# Reflow_Control_Board.net
KiCad netlist of a schematic drawn in EAGLE
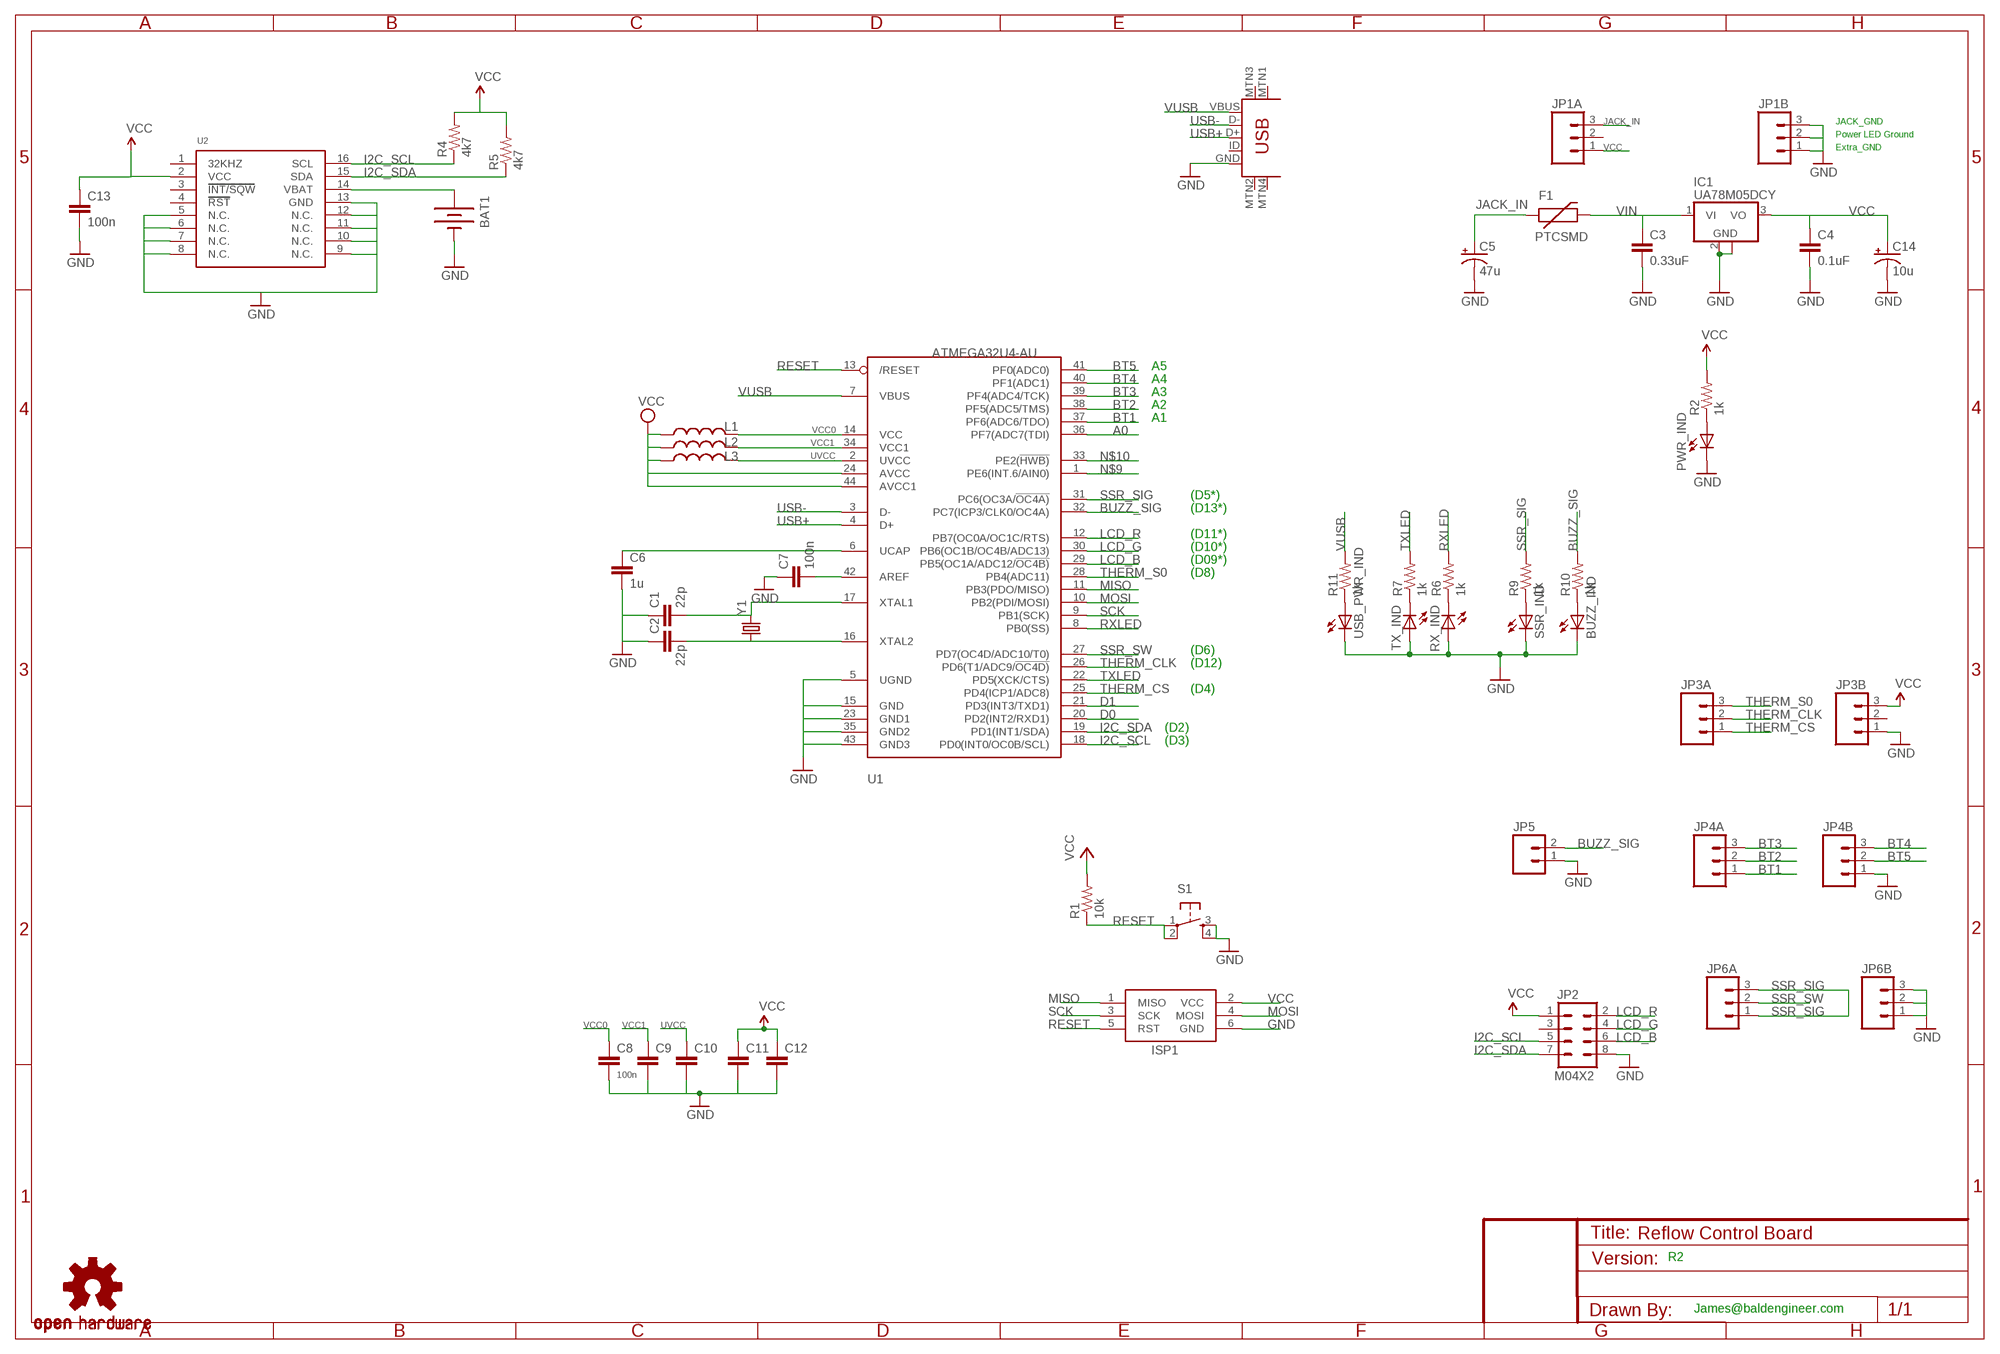
[diagram p0: schematic, sheet 1]

(export (version "E")
  (design (tool "Eeschema 10.0.6"))
  (components
    (comp (ref "BAT1")
      (value "BATTERY12MM")
      (footprint "eagle-import:BATTCON_12MM")
      (libsource (lib "eagle-import") (part "BATTERY12MM"))
    )
    (comp (ref "BUZZ_IND")
      (value "LED1206")
      (footprint "eagle-import:LED-1206")
      (libsource (lib "eagle-import") (part "LED1206"))
    )
    (comp (ref "C1")
      (value "22p")
      (footprint "eagle-import:1206")
      (libsource (lib "eagle-import") (part "CAP1206"))
    )
    (comp (ref "C2")
      (value "22p")
      (footprint "eagle-import:1206")
      (libsource (lib "eagle-import") (part "CAP1206"))
    )
    (comp (ref "C3")
      (value "0.33uF")
      (footprint "eagle-import:1206")
      (libsource (lib "eagle-import") (part "CAP1206"))
    )
    (comp (ref "C4")
      (value "0.1uF")
      (footprint "eagle-import:1206")
      (libsource (lib "eagle-import") (part "CAP1206"))
    )
    (comp (ref "C5")
      (value "47u")
      (footprint "eagle-import:D_7343-31R")
      (libsource (lib "eagle-import") (part "CPOL-USD/7343-31R"))
    )
    (comp (ref "C6")
      (value "1u")
      (footprint "eagle-import:1206")
      (libsource (lib "eagle-import") (part "CAP1206"))
    )
    (comp (ref "C7")
      (value "100n")
      (footprint "eagle-import:1206")
      (libsource (lib "eagle-import") (part "CAP1206"))
    )
    (comp (ref "C8")
      (value "100n")
      (footprint "eagle-import:1206")
      (libsource (lib "eagle-import") (part "CAP1206"))
    )
    (comp (ref "C9")
      (value "100n")
      (footprint "eagle-import:1206")
      (libsource (lib "eagle-import") (part "CAP1206"))
    )
    (comp (ref "C10")
      (value "100n")
      (footprint "eagle-import:1206")
      (libsource (lib "eagle-import") (part "CAP1206"))
    )
    (comp (ref "C11")
      (value "100n")
      (footprint "eagle-import:1206")
      (libsource (lib "eagle-import") (part "CAP1206"))
    )
    (comp (ref "C12")
      (value "100n")
      (footprint "eagle-import:1206")
      (libsource (lib "eagle-import") (part "CAP1206"))
    )
    (comp (ref "C13")
      (value "100n")
      (footprint "eagle-import:1206")
      (libsource (lib "eagle-import") (part "CAP1206"))
    )
    (comp (ref "C14")
      (value "10u")
      (footprint "eagle-import:D_7343-31R")
      (libsource (lib "eagle-import") (part "CPOL-USD/7343-31R"))
    )
    (comp (ref "F1")
      (value "PTCSMD")
      (footprint "eagle-import:PTC-1206")
      (libsource (lib "eagle-import") (part "PTCSMD"))
    )
    (comp (ref "IC1")
      (value "UA78M05DCY")
      (footprint "eagle-import:SOT223")
      (libsource (lib "eagle-import") (part "UA78MDCY05"))
    )
    (comp (ref "ISP1")
      (value "AVRISP-6")
      (footprint "eagle-import:AVRISP")
      (libsource (lib "eagle-import") (part "AVRISP-6"))
    )
    (comp (ref "JP1A")
      (value "M03LOCK")
      (footprint "eagle-import:1X03_LOCK")
      (libsource (lib "eagle-import") (part "M03LOCK"))
    )
    (comp (ref "JP1B")
      (value "M03LOCK")
      (footprint "eagle-import:1X03_LOCK")
      (libsource (lib "eagle-import") (part "M03LOCK"))
    )
    (comp (ref "JP2")
      (value "M04X2")
      (footprint "eagle-import:2X4")
      (libsource (lib "eagle-import") (part "M04X2"))
    )
    (comp (ref "JP3A")
      (value "M03LOCK")
      (footprint "eagle-import:1X03_LOCK")
      (libsource (lib "eagle-import") (part "M03LOCK"))
    )
    (comp (ref "JP3B")
      (value "M03LOCK")
      (footprint "eagle-import:1X03_LOCK")
      (libsource (lib "eagle-import") (part "M03LOCK"))
    )
    (comp (ref "JP4A")
      (value "M03LOCK")
      (footprint "eagle-import:1X03_LOCK")
      (libsource (lib "eagle-import") (part "M03LOCK"))
    )
    (comp (ref "JP4B")
      (value "M03LOCK")
      (footprint "eagle-import:1X03_LOCK")
      (libsource (lib "eagle-import") (part "M03LOCK"))
    )
    (comp (ref "JP5")
      (value "M02LOCK")
      (footprint "eagle-import:1X02_LOCK")
      (libsource (lib "eagle-import") (part "M02LOCK"))
    )
    (comp (ref "JP6A")
      (value "M03LOCK")
      (footprint "eagle-import:1X03_LOCK")
      (libsource (lib "eagle-import") (part "M03LOCK"))
    )
    (comp (ref "JP6B")
      (value "M03LOCK")
      (footprint "eagle-import:1X03_LOCK")
      (libsource (lib "eagle-import") (part "M03LOCK"))
    )
    (comp (ref "L1")
      (value "INDUCTOR0805")
      (footprint "eagle-import:0805")
      (libsource (lib "eagle-import") (part "INDUCTOR0805"))
    )
    (comp (ref "L2")
      (value "INDUCTOR0805")
      (footprint "eagle-import:0805")
      (libsource (lib "eagle-import") (part "INDUCTOR0805"))
    )
    (comp (ref "L3")
      (value "INDUCTOR0805")
      (footprint "eagle-import:0805")
      (libsource (lib "eagle-import") (part "INDUCTOR0805"))
    )
    (comp (ref "PWR_IND")
      (value "LED1206")
      (footprint "eagle-import:LED-1206")
      (libsource (lib "eagle-import") (part "LED1206"))
    )
    (comp (ref "R1")
      (value "10k")
      (footprint "eagle-import:1206")
      (libsource (lib "eagle-import") (part "RESISTOR1206"))
    )
    (comp (ref "R2")
      (value "1k")
      (footprint "eagle-import:1206")
      (libsource (lib "eagle-import") (part "RESISTOR1206"))
    )
    (comp (ref "R4")
      (value "4k7")
      (footprint "eagle-import:1206")
      (libsource (lib "eagle-import") (part "RESISTOR1206"))
    )
    (comp (ref "R5")
      (value "4k7")
      (footprint "eagle-import:1206")
      (libsource (lib "eagle-import") (part "RESISTOR1206"))
    )
    (comp (ref "R6")
      (value "1k")
      (footprint "eagle-import:1206")
      (libsource (lib "eagle-import") (part "RESISTOR1206"))
    )
    (comp (ref "R7")
      (value "1k")
      (footprint "eagle-import:1206")
      (libsource (lib "eagle-import") (part "RESISTOR1206"))
    )
    (comp (ref "R9")
      (value "1k")
      (footprint "eagle-import:1206")
      (libsource (lib "eagle-import") (part "RESISTOR1206"))
    )
    (comp (ref "R10")
      (value "1k")
      (footprint "eagle-import:1206")
      (libsource (lib "eagle-import") (part "RESISTOR1206"))
    )
    (comp (ref "R11")
      (value "1k")
      (footprint "eagle-import:1206")
      (libsource (lib "eagle-import") (part "RESISTOR1206"))
    )
    (comp (ref "RX_IND")
      (value "LED1206")
      (footprint "eagle-import:LED-1206")
      (libsource (lib "eagle-import") (part "LED1206"))
    )
    (comp (ref "S1")
      (value "TAC_SWITCHSMD")
      (footprint "eagle-import:TACTILE_SWITCH_SMD")
      (libsource (lib "eagle-import") (part "TAC_SWITCHSMD"))
    )
    (comp (ref "SSR_IND")
      (value "LED1206")
      (footprint "eagle-import:LED-1206")
      (libsource (lib "eagle-import") (part "LED1206"))
    )
    (comp (ref "TX_IND")
      (value "LED1206")
      (footprint "eagle-import:LED-1206")
      (libsource (lib "eagle-import") (part "LED1206"))
    )
    (comp (ref "U$3")
      (value "USB-MINIB-5PIN")
      (footprint "eagle-import:USB-MINIB")
      (libsource (lib "eagle-import") (part "USB-MINIB-5PIN"))
    )
    (comp (ref "U$4")
      (value "OSHW-LOGOS")
      (footprint "eagle-import:OSHW-LOGO-S")
      (libsource (lib "eagle-import") (part "OSHW-LOGOS"))
    )
    (comp (ref "U1")
      (value "ATMEGA32U4-AU")
      (footprint "eagle-import:TQFP44")
      (libsource (lib "eagle-import") (part "ATMEGA32U4-AU"))
    )
    (comp (ref "U2")
      (value "DS3231")
      (footprint "eagle-import:SO16L")
      (libsource (lib "eagle-import") (part "DS3231"))
    )
    (comp (ref "USB_PWR_IND")
      (value "LED1206")
      (footprint "eagle-import:LED-1206")
      (libsource (lib "eagle-import") (part "LED1206"))
    )
    (comp (ref "Y1")
      (value "CRYSTALHC49US")
      (footprint "eagle-import:HC49US")
      (libsource (lib "eagle-import") (part "CRYSTALHC49US"))
    )
  )
  (nets
    (net (code "1") (name "/A0") (class "Default")
      (node (ref "U1") (pin "36") (pinfunction "PF7(ADC7(TDI)_36") (pintype "bidirectional"))
    )
    (net (code "2") (name "/BT1") (class "Default")
      (node (ref "JP4A") (pin "1") (pinfunction "1_1") (pintype "passive"))
      (node (ref "U1") (pin "37") (pinfunction "PF6(ADC6/TDO)_37") (pintype "bidirectional"))
    )
    (net (code "3") (name "/BT2") (class "Default")
      (node (ref "JP4A") (pin "2") (pinfunction "2_2") (pintype "passive"))
      (node (ref "U1") (pin "38") (pinfunction "PF5(ADC5/TMS)_38") (pintype "bidirectional"))
    )
    (net (code "4") (name "/BT3") (class "Default")
      (node (ref "JP4A") (pin "3") (pinfunction "3_3") (pintype "passive"))
      (node (ref "U1") (pin "39") (pinfunction "PF4(ADC4/TCK)_39") (pintype "bidirectional"))
    )
    (net (code "5") (name "/BT4") (class "Default")
      (node (ref "JP4B") (pin "3") (pinfunction "3_3") (pintype "passive"))
      (node (ref "U1") (pin "40") (pinfunction "PF1(ADC1)_40") (pintype "bidirectional"))
    )
    (net (code "6") (name "/BT5") (class "Default")
      (node (ref "JP4B") (pin "2") (pinfunction "2_2") (pintype "passive"))
      (node (ref "U1") (pin "41") (pinfunction "PF0(ADC0)_41") (pintype "bidirectional"))
    )
    (net (code "7") (name "/BUZZ_SIG") (class "Default")
      (node (ref "JP5") (pin "2") (pinfunction "2_2") (pintype "passive"))
      (node (ref "R10") (pin "2") (pinfunction "2_2") (pintype "passive"))
      (node (ref "U1") (pin "32") (pinfunction "PC7(ICP3/CLK0/OC4A)_32") (pintype "bidirectional"))
    )
    (net (code "8") (name "/D0") (class "Default")
      (node (ref "U1") (pin "20") (pinfunction "PD2(INT2/RXD1)_20") (pintype "bidirectional"))
    )
    (net (code "9") (name "/D1") (class "Default")
      (node (ref "U1") (pin "21") (pinfunction "PD3(INT3/TXD1)_21") (pintype "bidirectional"))
    )
    (net (code "10") (name "/I2C_SCL") (class "Default")
      (node (ref "JP2") (pin "5") (pinfunction "5_5") (pintype "passive"))
      (node (ref "R4") (pin "1") (pinfunction "1_1") (pintype "passive"))
      (node (ref "U1") (pin "18") (pinfunction "PD0(INT0/OC0B/SCL)_18") (pintype "bidirectional"))
      (node (ref "U2") (pin "16") (pinfunction "SCL_16") (pintype "bidirectional"))
    )
    (net (code "11") (name "/I2C_SDA") (class "Default")
      (node (ref "JP2") (pin "7") (pinfunction "7_7") (pintype "passive"))
      (node (ref "R5") (pin "1") (pinfunction "1_1") (pintype "passive"))
      (node (ref "U1") (pin "19") (pinfunction "PD1(INT1/SDA)_19") (pintype "bidirectional"))
      (node (ref "U2") (pin "15") (pinfunction "SDA_15") (pintype "bidirectional"))
    )
    (net (code "12") (name "/JACK_IN") (class "Default")
      (node (ref "C5") (pin "+") (pinfunction "+_+") (pintype "passive"))
      (node (ref "F1") (pin "1") (pinfunction "1_1") (pintype "bidirectional"))
      (node (ref "JP1A") (pin "3") (pinfunction "3_3") (pintype "passive"))
    )
    (net (code "13") (name "/LCD_B") (class "Default")
      (node (ref "JP2") (pin "6") (pinfunction "6_6") (pintype "passive"))
      (node (ref "U1") (pin "29") (pinfunction "PB5(OC1A/ADC12/~{OC4B})_29") (pintype "bidirectional"))
    )
    (net (code "14") (name "/LCD_G") (class "Default")
      (node (ref "JP2") (pin "4") (pinfunction "4_4") (pintype "passive"))
      (node (ref "U1") (pin "30") (pinfunction "PB6(OC1B/OC4B/ADC13)_30") (pintype "bidirectional"))
    )
    (net (code "15") (name "/LCD_R") (class "Default")
      (node (ref "JP2") (pin "2") (pinfunction "2_2") (pintype "passive"))
      (node (ref "U1") (pin "12") (pinfunction "PB7(OC0A/OC1C/RTS)_12") (pintype "bidirectional"))
    )
    (net (code "16") (name "/MISO") (class "Default")
      (node (ref "ISP1") (pin "1") (pinfunction "MISO_1") (pintype "input"))
      (node (ref "U1") (pin "11") (pinfunction "PB3(PDO/MISO)_11") (pintype "bidirectional"))
    )
    (net (code "17") (name "/MOSI") (class "Default")
      (node (ref "ISP1") (pin "4") (pinfunction "MOSI_4") (pintype "output"))
      (node (ref "U1") (pin "10") (pinfunction "PB2(PDI/MOSI)_10") (pintype "bidirectional"))
    )
    (net (code "18") (name "/N$9") (class "Default")
      (node (ref "U1") (pin "1") (pinfunction "PE6(INT.6/AIN0)_1") (pintype "bidirectional"))
    )
    (net (code "19") (name "/N$10") (class "Default")
      (node (ref "U1") (pin "33") (pinfunction "PE2(~{HWB})_33") (pintype "bidirectional"))
    )
    (net (code "20") (name "/RESET") (class "Default")
      (node (ref "ISP1") (pin "5") (pinfunction "RST_5") (pintype "output"))
      (node (ref "R1") (pin "1") (pinfunction "1_1") (pintype "passive"))
      (node (ref "S1") (pin "1") (pinfunction "1_1") (pintype "passive"))
      (node (ref "S1") (pin "2") (pinfunction "2_2") (pintype "passive"))
      (node (ref "U1") (pin "13") (pinfunction "/RESET_13") (pintype "bidirectional"))
    )
    (net (code "21") (name "/RXLED") (class "Default")
      (node (ref "R6") (pin "2") (pinfunction "2_2") (pintype "passive"))
      (node (ref "U1") (pin "8") (pinfunction "PB0(SS)_8") (pintype "bidirectional"))
    )
    (net (code "22") (name "/SCK") (class "Default")
      (node (ref "ISP1") (pin "3") (pinfunction "SCK_3") (pintype "output"))
      (node (ref "U1") (pin "9") (pinfunction "PB1(SCK)_9") (pintype "bidirectional"))
    )
    (net (code "23") (name "/SSR_SIG") (class "Default")
      (node (ref "JP6A") (pin "1") (pinfunction "1_1") (pintype "passive"))
      (node (ref "JP6A") (pin "3") (pinfunction "3_3") (pintype "passive"))
      (node (ref "R9") (pin "2") (pinfunction "2_2") (pintype "passive"))
      (node (ref "U1") (pin "31") (pinfunction "PC6(OC3A/~{OC4A})_31") (pintype "bidirectional"))
    )
    (net (code "24") (name "/SSR_SW") (class "Default")
      (node (ref "JP6A") (pin "2") (pinfunction "2_2") (pintype "passive"))
      (node (ref "U1") (pin "27") (pinfunction "PD7(OC4D/ADC10/T0)_27") (pintype "bidirectional"))
    )
    (net (code "25") (name "/THERM_CLK") (class "Default")
      (node (ref "JP3A") (pin "2") (pinfunction "2_2") (pintype "passive"))
      (node (ref "U1") (pin "26") (pinfunction "PD6(T1/ADC9/~{OC4D})_26") (pintype "bidirectional"))
    )
    (net (code "26") (name "/THERM_CS") (class "Default")
      (node (ref "JP3A") (pin "1") (pinfunction "1_1") (pintype "passive"))
      (node (ref "U1") (pin "25") (pinfunction "PD4(ICP1/ADC8)_25") (pintype "bidirectional"))
    )
    (net (code "27") (name "/THERM_S0") (class "Default")
      (node (ref "JP3A") (pin "3") (pinfunction "3_3") (pintype "passive"))
      (node (ref "U1") (pin "28") (pinfunction "PB4(ADC11)_28") (pintype "bidirectional"))
    )
    (net (code "28") (name "/TXLED") (class "Default")
      (node (ref "R7") (pin "2") (pinfunction "2_2") (pintype "passive"))
      (node (ref "U1") (pin "22") (pinfunction "PD5(XCK/CTS)_22") (pintype "bidirectional"))
    )
    (net (code "29") (name "/USB+") (class "Default")
      (node (ref "U$3") (pin "D+") (pinfunction "D+_D+") (pintype "bidirectional"))
      (node (ref "U1") (pin "4") (pinfunction "D+_4") (pintype "bidirectional"))
    )
    (net (code "30") (name "/USB-") (class "Default")
      (node (ref "U$3") (pin "D-") (pinfunction "D-_D-") (pintype "bidirectional"))
      (node (ref "U1") (pin "3") (pinfunction "D-_3") (pintype "bidirectional"))
    )
    (net (code "31") (name "/UVCC") (class "Default")
      (node (ref "C10") (pin "1") (pinfunction "1_1") (pintype "passive"))
      (node (ref "L3") (pin "2") (pinfunction "2_2") (pintype "passive"))
      (node (ref "U1") (pin "2") (pinfunction "UVCC_2") (pintype "bidirectional"))
    )
    (net (code "32") (name "/VCC0") (class "Default")
      (node (ref "C8") (pin "1") (pinfunction "1_1") (pintype "passive"))
      (node (ref "L1") (pin "2") (pinfunction "2_2") (pintype "passive"))
      (node (ref "U1") (pin "14") (pinfunction "VCC_14") (pintype "bidirectional"))
    )
    (net (code "33") (name "/VCC1") (class "Default")
      (node (ref "C9") (pin "1") (pinfunction "1_1") (pintype "passive"))
      (node (ref "L2") (pin "2") (pinfunction "2_2") (pintype "passive"))
      (node (ref "U1") (pin "34") (pinfunction "VCC1_34") (pintype "bidirectional"))
    )
    (net (code "34") (name "/VIN") (class "Default")
      (node (ref "C3") (pin "1") (pinfunction "1_1") (pintype "passive"))
      (node (ref "F1") (pin "2") (pinfunction "2_2") (pintype "bidirectional"))
      (node (ref "IC1") (pin "1") (pinfunction "VI_1") (pintype "input"))
    )
    (net (code "35") (name "/VUSB") (class "Default")
      (node (ref "R11") (pin "2") (pinfunction "2_2") (pintype "passive"))
      (node (ref "U$3") (pin "VBUS") (pinfunction "VBUS_VBUS") (pintype "bidirectional"))
      (node (ref "U1") (pin "7") (pinfunction "VBUS_7") (pintype "bidirectional"))
    )
    (net (code "36") (name "GND") (class "Default")
      (node (ref "BAT1") (pin "GND") (pinfunction "-_GND") (pintype "power_in"))
      (node (ref "BUZZ_IND") (pin "C") (pinfunction "C_C") (pintype "passive"))
      (node (ref "C1") (pin "1") (pinfunction "1_1") (pintype "passive"))
      (node (ref "C10") (pin "2") (pinfunction "2_2") (pintype "passive"))
      (node (ref "C11") (pin "2") (pinfunction "2_2") (pintype "passive"))
      (node (ref "C12") (pin "2") (pinfunction "2_2") (pintype "passive"))
      (node (ref "C13") (pin "2") (pinfunction "2_2") (pintype "passive"))
      (node (ref "C14") (pin "-") (pinfunction "-_-") (pintype "passive"))
      (node (ref "C2") (pin "1") (pinfunction "1_1") (pintype "passive"))
      (node (ref "C3") (pin "2") (pinfunction "2_2") (pintype "passive"))
      (node (ref "C4") (pin "2") (pinfunction "2_2") (pintype "passive"))
      (node (ref "C5") (pin "-") (pinfunction "-_-") (pintype "passive"))
      (node (ref "C6") (pin "2") (pinfunction "2_2") (pintype "passive"))
      (node (ref "C7") (pin "1") (pinfunction "1_1") (pintype "passive"))
      (node (ref "C8") (pin "2") (pinfunction "2_2") (pintype "passive"))
      (node (ref "C9") (pin "2") (pinfunction "2_2") (pintype "passive"))
      (node (ref "IC1") (pin "2") (pinfunction "GND_2") (pintype "passive"))
      (node (ref "IC1") (pin "4") (pinfunction "GND_4") (pintype "passive"))
      (node (ref "ISP1") (pin "6") (pinfunction "GND_6") (pintype "power_in"))
      (node (ref "JP1B") (pin "1") (pinfunction "1_1") (pintype "passive"))
      (node (ref "JP1B") (pin "2") (pinfunction "2_2") (pintype "passive"))
      (node (ref "JP1B") (pin "3") (pinfunction "3_3") (pintype "passive"))
      (node (ref "JP2") (pin "8") (pinfunction "8_8") (pintype "passive"))
      (node (ref "JP3B") (pin "1") (pinfunction "1_1") (pintype "passive"))
      (node (ref "JP4B") (pin "1") (pinfunction "1_1") (pintype "passive"))
      (node (ref "JP5") (pin "1") (pinfunction "1_1") (pintype "passive"))
      (node (ref "JP6B") (pin "1") (pinfunction "1_1") (pintype "passive"))
      (node (ref "JP6B") (pin "2") (pinfunction "2_2") (pintype "passive"))
      (node (ref "JP6B") (pin "3") (pinfunction "3_3") (pintype "passive"))
      (node (ref "PWR_IND") (pin "C") (pinfunction "C_C") (pintype "passive"))
      (node (ref "RX_IND") (pin "A") (pinfunction "A_A") (pintype "passive"))
      (node (ref "S1") (pin "3") (pinfunction "3_3") (pintype "passive"))
      (node (ref "S1") (pin "4") (pinfunction "4_4") (pintype "passive"))
      (node (ref "SSR_IND") (pin "C") (pinfunction "C_C") (pintype "passive"))
      (node (ref "TX_IND") (pin "A") (pinfunction "A_A") (pintype "passive"))
      (node (ref "U$3") (pin "GND") (pinfunction "GND_GND") (pintype "bidirectional"))
      (node (ref "U1") (pin "15") (pinfunction "GND_15") (pintype "bidirectional"))
      (node (ref "U1") (pin "23") (pinfunction "GND1_23") (pintype "bidirectional"))
      (node (ref "U1") (pin "35") (pinfunction "GND2_35") (pintype "bidirectional"))
      (node (ref "U1") (pin "43") (pinfunction "GND3_43") (pintype "bidirectional"))
      (node (ref "U1") (pin "5") (pinfunction "UGND_5") (pintype "bidirectional"))
      (node (ref "U2") (pin "10") (pinfunction "N.C._10") (pintype "bidirectional"))
      (node (ref "U2") (pin "11") (pinfunction "N.C._11") (pintype "bidirectional"))
      (node (ref "U2") (pin "12") (pinfunction "N.C._12") (pintype "bidirectional"))
      (node (ref "U2") (pin "13") (pinfunction "GND_13") (pintype "power_in"))
      (node (ref "U2") (pin "5") (pinfunction "N.C._5") (pintype "bidirectional"))
      (node (ref "U2") (pin "6") (pinfunction "N.C._6") (pintype "bidirectional"))
      (node (ref "U2") (pin "7") (pinfunction "N.C._7") (pintype "bidirectional"))
      (node (ref "U2") (pin "8") (pinfunction "N.C._8") (pintype "bidirectional"))
      (node (ref "U2") (pin "9") (pinfunction "N.C._9") (pintype "bidirectional"))
      (node (ref "USB_PWR_IND") (pin "C") (pinfunction "C_C") (pintype "passive"))
    )
    (net (code "37") (name "Net-(BAT1-+)") (class "Default")
      (node (ref "BAT1") (pin "PWR@2") (pinfunction "+_PWR@2") (pintype "power_in"))
      (node (ref "U2") (pin "14") (pinfunction "VBAT_14") (pintype "power_in"))
    )
    (net (code "38") (name "Net-(BUZZ_IND-PadA)") (class "Default")
      (node (ref "BUZZ_IND") (pin "A") (pinfunction "A_A") (pintype "passive"))
      (node (ref "R10") (pin "1") (pinfunction "1_1") (pintype "passive"))
    )
    (net (code "39") (name "Net-(PWR_IND-PadA)") (class "Default")
      (node (ref "PWR_IND") (pin "A") (pinfunction "A_A") (pintype "passive"))
      (node (ref "R2") (pin "1") (pinfunction "1_1") (pintype "passive"))
    )
    (net (code "40") (name "Net-(R6-Pad1)") (class "Default")
      (node (ref "R6") (pin "1") (pinfunction "1_1") (pintype "passive"))
      (node (ref "RX_IND") (pin "C") (pinfunction "C_C") (pintype "passive"))
    )
    (net (code "41") (name "Net-(R7-Pad1)") (class "Default")
      (node (ref "R7") (pin "1") (pinfunction "1_1") (pintype "passive"))
      (node (ref "TX_IND") (pin "C") (pinfunction "C_C") (pintype "passive"))
    )
    (net (code "42") (name "Net-(R9-Pad1)") (class "Default")
      (node (ref "R9") (pin "1") (pinfunction "1_1") (pintype "passive"))
      (node (ref "SSR_IND") (pin "A") (pinfunction "A_A") (pintype "passive"))
    )
    (net (code "43") (name "Net-(R11-Pad1)") (class "Default")
      (node (ref "R11") (pin "1") (pinfunction "1_1") (pintype "passive"))
      (node (ref "USB_PWR_IND") (pin "A") (pinfunction "A_A") (pintype "passive"))
    )
    (net (code "44") (name "Net-(U1-AREF)") (class "Default")
      (node (ref "C7") (pin "2") (pinfunction "2_2") (pintype "passive"))
      (node (ref "U1") (pin "42") (pinfunction "AREF_42") (pintype "bidirectional"))
    )
    (net (code "45") (name "Net-(U1-UCAP)") (class "Default")
      (node (ref "C6") (pin "1") (pinfunction "1_1") (pintype "passive"))
      (node (ref "U1") (pin "6") (pinfunction "UCAP_6") (pintype "bidirectional"))
    )
    (net (code "46") (name "Net-(U1-XTAL1)") (class "Default")
      (node (ref "C1") (pin "2") (pinfunction "2_2") (pintype "passive"))
      (node (ref "U1") (pin "17") (pinfunction "XTAL1_17") (pintype "bidirectional"))
      (node (ref "Y1") (pin "2") (pinfunction "2_2") (pintype "passive"))
    )
    (net (code "47") (name "Net-(U1-XTAL2)") (class "Default")
      (node (ref "C2") (pin "2") (pinfunction "2_2") (pintype "passive"))
      (node (ref "U1") (pin "16") (pinfunction "XTAL2_16") (pintype "bidirectional"))
      (node (ref "Y1") (pin "1") (pinfunction "1_1") (pintype "passive"))
    )
    (net (code "48") (name "VCC") (class "Default")
      (node (ref "C11") (pin "1") (pinfunction "1_1") (pintype "passive"))
      (node (ref "C12") (pin "1") (pinfunction "1_1") (pintype "passive"))
      (node (ref "C13") (pin "1") (pinfunction "1_1") (pintype "passive"))
      (node (ref "C14") (pin "+") (pinfunction "+_+") (pintype "passive"))
      (node (ref "C4") (pin "1") (pinfunction "1_1") (pintype "passive"))
      (node (ref "IC1") (pin "3") (pinfunction "VO_3") (pintype "passive"))
      (node (ref "ISP1") (pin "2") (pinfunction "VCC_2") (pintype "power_in"))
      (node (ref "JP1A") (pin "1") (pinfunction "1_1") (pintype "passive"))
      (node (ref "JP2") (pin "1") (pinfunction "1_1") (pintype "passive"))
      (node (ref "JP3B") (pin "3") (pinfunction "3_3") (pintype "passive"))
      (node (ref "L1") (pin "1") (pinfunction "1_1") (pintype "passive"))
      (node (ref "L2") (pin "1") (pinfunction "1_1") (pintype "passive"))
      (node (ref "L3") (pin "1") (pinfunction "1_1") (pintype "passive"))
      (node (ref "R1") (pin "2") (pinfunction "2_2") (pintype "passive"))
      (node (ref "R2") (pin "2") (pinfunction "2_2") (pintype "passive"))
      (node (ref "R4") (pin "2") (pinfunction "2_2") (pintype "passive"))
      (node (ref "R5") (pin "2") (pinfunction "2_2") (pintype "passive"))
      (node (ref "U1") (pin "24") (pinfunction "AVCC_24") (pintype "bidirectional"))
      (node (ref "U1") (pin "44") (pinfunction "AVCC1_44") (pintype "bidirectional"))
      (node (ref "U2") (pin "2") (pinfunction "VCC_2") (pintype "power_in"))
    )
    (net (code "49") (name "unconnected-(JP1A-Pad2)") (class "Default")
      (node (ref "JP1A") (pin "2") (pinfunction "2_2") (pintype "passive"))
    )
    (net (code "50") (name "unconnected-(JP2-Pad3)") (class "Default")
      (node (ref "JP2") (pin "3") (pinfunction "3_3") (pintype "passive"))
    )
    (net (code "51") (name "unconnected-(JP3B-Pad2)") (class "Default")
      (node (ref "JP3B") (pin "2") (pinfunction "2_2") (pintype "passive"))
    )
    (net (code "52") (name "unconnected-(U$3-MTN1-PadMTN3)") (class "Default")
      (node (ref "U$3") (pin "MTN3") (pinfunction "MTN1_MTN3") (pintype "bidirectional"))
    )
    (net (code "53") (name "unconnected-(U$3-MTN2-PadMTN1)") (class "Default")
      (node (ref "U$3") (pin "MTN1") (pinfunction "MTN2_MTN1") (pintype "bidirectional"))
    )
    (net (code "54") (name "unconnected-(U$3-MTN3-PadMTN2)") (class "Default")
      (node (ref "U$3") (pin "MTN2") (pinfunction "MTN3_MTN2") (pintype "bidirectional"))
    )
    (net (code "55") (name "unconnected-(U$3-PadID)") (class "Default")
      (node (ref "U$3") (pin "ID") (pinfunction "ID_ID") (pintype "bidirectional"))
    )
    (net (code "56") (name "unconnected-(U$3-PadMTN4)") (class "Default")
      (node (ref "U$3") (pin "MTN4") (pinfunction "MTN4_MTN4") (pintype "bidirectional"))
    )
    (net (code "57") (name "unconnected-(U2-32KHZ-Pad1)") (class "Default")
      (node (ref "U2") (pin "1") (pinfunction "32KHZ_1") (pintype "bidirectional"))
    )
    (net (code "58") (name "unconnected-(U2-INT{slash}SQW-Pad3)") (class "Default")
      (node (ref "U2") (pin "3") (pinfunction "INT/SQW_3") (pintype "bidirectional"))
    )
    (net (code "59") (name "unconnected-(U2-RST-Pad4)") (class "Default")
      (node (ref "U2") (pin "4") (pinfunction "RST_4") (pintype "bidirectional"))
    )
  )
)
